# Lock.net
KiCad netlist of a schematic drawn in EAGLE
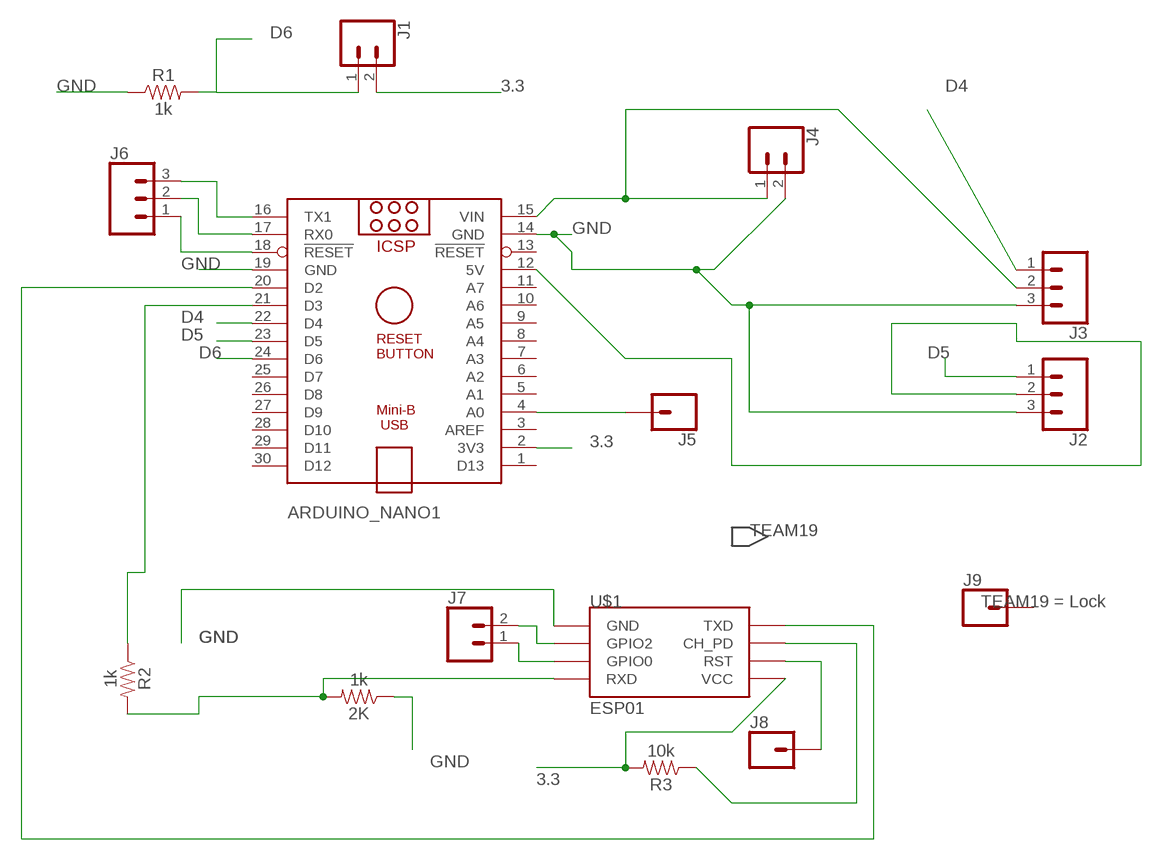
[diagram p0: schematic, sheet 1]

(export (version "E")
  (design (tool "Eeschema 10.0.6"))
  (components
    (comp (ref "2K")
      (value "1k")
      (footprint "eagle-import:AXIAL-0.3")
      (libsource (lib "eagle-import") (part "1KOHM-HORIZ-1/4W-1%"))
    )
    (comp (ref "ARDUINO_NANO1")
      (value "ARDUINO_NANO")
      (footprint "eagle-import:ARDUINO_NANO")
      (libsource (lib "eagle-import") (part "ARDUINO_NANO"))
    )
    (comp (ref "J1")
      (value "CONN_02")
      (footprint "eagle-import:1X02")
      (libsource (lib "eagle-import") (part "CONN_02"))
    )
    (comp (ref "J2")
      (value "CONN_03")
      (footprint "eagle-import:1X03")
      (libsource (lib "eagle-import") (part "CONN_03"))
    )
    (comp (ref "J3")
      (value "CONN_03")
      (footprint "eagle-import:1X03")
      (libsource (lib "eagle-import") (part "CONN_03"))
    )
    (comp (ref "J4")
      (value "CONN_02")
      (footprint "eagle-import:1X02")
      (libsource (lib "eagle-import") (part "CONN_02"))
    )
    (comp (ref "J5")
      (value "CONN_01")
      (footprint "eagle-import:1X01")
      (libsource (lib "eagle-import") (part "CONN_01"))
    )
    (comp (ref "J6")
      (value "CONN_03")
      (footprint "eagle-import:1X03")
      (libsource (lib "eagle-import") (part "CONN_03"))
    )
    (comp (ref "J7")
      (value "CONN_02")
      (footprint "eagle-import:1X02")
      (libsource (lib "eagle-import") (part "CONN_02"))
    )
    (comp (ref "J8")
      (value "CONN_01")
      (footprint "eagle-import:1X01")
      (libsource (lib "eagle-import") (part "CONN_01"))
    )
    (comp (ref "J9")
      (value "CONN_01")
      (footprint "eagle-import:1X01")
      (fields (field (name "TEAM19") "Lock"))
      (libsource (lib "eagle-import") (part "CONN_01"))
    )
    (comp (ref "R1")
      (value "1k")
      (footprint "eagle-import:AXIAL-0.3")
      (libsource (lib "eagle-import") (part "1KOHM-HORIZ-1/4W-1%"))
    )
    (comp (ref "R2")
      (value "1k")
      (footprint "eagle-import:AXIAL-0.3")
      (libsource (lib "eagle-import") (part "1KOHM-HORIZ-1/4W-1%"))
    )
    (comp (ref "R3")
      (value "10k")
      (footprint "eagle-import:AXIAL-0.3")
      (libsource (lib "eagle-import") (part "10KOHM-HORIZ-1/4W-1%"))
    )
    (comp (ref "U$1")
      (value "ESP01")
      (footprint "eagle-import:ESP01")
      (libsource (lib "eagle-import") (part "ESP01"))
    )
  )
  (nets
    (net (code "1") (name "/3.3") (class "Default")
      (node (ref "ARDUINO_NANO1") (pin "2") (pinfunction "3V3_2") (pintype "output"))
      (node (ref "J1") (pin "2") (pinfunction "2_2") (pintype "passive"))
      (node (ref "R3") (pin "P$2") (pinfunction "2_P$2") (pintype "passive"))
      (node (ref "U$1") (pin "VCC") (pinfunction "VCC_VCC") (pintype "bidirectional"))
    )
    (net (code "2") (name "/D4") (class "Default")
      (node (ref "ARDUINO_NANO1") (pin "22") (pinfunction "D4_22") (pintype "bidirectional"))
      (node (ref "J3") (pin "1") (pinfunction "1_1") (pintype "passive"))
    )
    (net (code "3") (name "/D5") (class "Default")
      (node (ref "ARDUINO_NANO1") (pin "23") (pinfunction "D5_23") (pintype "bidirectional"))
      (node (ref "J2") (pin "1") (pinfunction "1_1") (pintype "passive"))
    )
    (net (code "4") (name "/D6") (class "Default")
      (node (ref "ARDUINO_NANO1") (pin "24") (pinfunction "D6_24") (pintype "bidirectional"))
      (node (ref "J1") (pin "1") (pinfunction "1_1") (pintype "passive"))
      (node (ref "R1") (pin "P$2") (pinfunction "2_P$2") (pintype "passive"))
    )
    (net (code "5") (name "/GND") (class "Default")
      (node (ref "2K") (pin "P$1") (pinfunction "1_P$1") (pintype "passive"))
      (node (ref "ARDUINO_NANO1") (pin "14") (pinfunction "GND_14") (pintype "power_in"))
      (node (ref "ARDUINO_NANO1") (pin "19") (pinfunction "GND_19") (pintype "power_in"))
      (node (ref "J2") (pin "3") (pinfunction "3_3") (pintype "passive"))
      (node (ref "J3") (pin "3") (pinfunction "3_3") (pintype "passive"))
      (node (ref "J4") (pin "2") (pinfunction "2_2") (pintype "passive"))
      (node (ref "R1") (pin "P$1") (pinfunction "1_P$1") (pintype "passive"))
      (node (ref "U$1") (pin "GND") (pinfunction "GND_GND") (pintype "bidirectional"))
    )
    (net (code "6") (name "Net-(2K-2)") (class "Default")
      (node (ref "2K") (pin "P$2") (pinfunction "2_P$2") (pintype "passive"))
      (node (ref "R2") (pin "P$2") (pinfunction "2_P$2") (pintype "passive"))
      (node (ref "U$1") (pin "RX") (pinfunction "RXD_RX") (pintype "bidirectional"))
    )
    (net (code "7") (name "Net-(ARDUINO_NANO1-5V)") (class "Default")
      (node (ref "ARDUINO_NANO1") (pin "12") (pinfunction "5V_12") (pintype "power_in"))
      (node (ref "J2") (pin "2") (pinfunction "2_2") (pintype "passive"))
    )
    (net (code "8") (name "Net-(ARDUINO_NANO1-A0)") (class "Default")
      (node (ref "ARDUINO_NANO1") (pin "4") (pinfunction "A0_4") (pintype "bidirectional"))
      (node (ref "J5") (pin "1") (pinfunction "1_1") (pintype "passive"))
    )
    (net (code "9") (name "Net-(ARDUINO_NANO1-D2)") (class "Default")
      (node (ref "ARDUINO_NANO1") (pin "20") (pinfunction "D2_20") (pintype "bidirectional"))
      (node (ref "U$1") (pin "TX") (pinfunction "TXD_TX") (pintype "bidirectional"))
    )
    (net (code "10") (name "Net-(ARDUINO_NANO1-D3)") (class "Default")
      (node (ref "ARDUINO_NANO1") (pin "21") (pinfunction "D3_21") (pintype "bidirectional"))
      (node (ref "R2") (pin "P$1") (pinfunction "1_P$1") (pintype "passive"))
    )
    (net (code "11") (name "Net-(ARDUINO_NANO1-RX0)") (class "Default")
      (node (ref "ARDUINO_NANO1") (pin "17") (pinfunction "RX0_17") (pintype "bidirectional"))
      (node (ref "J6") (pin "2") (pinfunction "2_2") (pintype "passive"))
    )
    (net (code "12") (name "Net-(ARDUINO_NANO1-TX1)") (class "Default")
      (node (ref "ARDUINO_NANO1") (pin "16") (pinfunction "TX1_16") (pintype "bidirectional"))
      (node (ref "J6") (pin "3") (pinfunction "3_3") (pintype "passive"))
    )
    (net (code "13") (name "Net-(ARDUINO_NANO1-VIN)") (class "Default")
      (node (ref "ARDUINO_NANO1") (pin "15") (pinfunction "VIN_15") (pintype "power_in"))
      (node (ref "J3") (pin "2") (pinfunction "2_2") (pintype "passive"))
      (node (ref "J4") (pin "1") (pinfunction "1_1") (pintype "passive"))
    )
    (net (code "14") (name "Net-(ARDUINO_NANO1-~{RESET}-Pad18)") (class "Default")
      (node (ref "ARDUINO_NANO1") (pin "18") (pinfunction "~{RESET}_18") (pintype "input"))
      (node (ref "J6") (pin "1") (pinfunction "1_1") (pintype "passive"))
    )
    (net (code "15") (name "Net-(J7-Pad1)") (class "Default")
      (node (ref "J7") (pin "1") (pinfunction "1_1") (pintype "passive"))
      (node (ref "U$1") (pin "GPIO0") (pinfunction "GPIO0_GPIO0") (pintype "bidirectional"))
    )
    (net (code "16") (name "Net-(J7-Pad2)") (class "Default")
      (node (ref "J7") (pin "2") (pinfunction "2_2") (pintype "passive"))
      (node (ref "U$1") (pin "GPIO2") (pinfunction "GPIO2_GPIO2") (pintype "bidirectional"))
    )
    (net (code "17") (name "Net-(J8-Pad1)") (class "Default")
      (node (ref "J8") (pin "1") (pinfunction "1_1") (pintype "passive"))
      (node (ref "U$1") (pin "RST") (pinfunction "RST_RST") (pintype "bidirectional"))
    )
    (net (code "18") (name "Net-(R3-1)") (class "Default")
      (node (ref "R3") (pin "P$1") (pinfunction "1_P$1") (pintype "passive"))
      (node (ref "U$1") (pin "CH_PD") (pinfunction "CH_PD_CH_PD") (pintype "bidirectional"))
    )
    (net (code "19") (name "unconnected-(ARDUINO_NANO1-A1-Pad5)") (class "Default")
      (node (ref "ARDUINO_NANO1") (pin "5") (pinfunction "A1_5") (pintype "bidirectional"))
    )
    (net (code "20") (name "unconnected-(ARDUINO_NANO1-A2-Pad6)") (class "Default")
      (node (ref "ARDUINO_NANO1") (pin "6") (pinfunction "A2_6") (pintype "bidirectional"))
    )
    (net (code "21") (name "unconnected-(ARDUINO_NANO1-A3-Pad7)") (class "Default")
      (node (ref "ARDUINO_NANO1") (pin "7") (pinfunction "A3_7") (pintype "bidirectional"))
    )
    (net (code "22") (name "unconnected-(ARDUINO_NANO1-A4-Pad8)") (class "Default")
      (node (ref "ARDUINO_NANO1") (pin "8") (pinfunction "A4_8") (pintype "bidirectional"))
    )
    (net (code "23") (name "unconnected-(ARDUINO_NANO1-A5-Pad9)") (class "Default")
      (node (ref "ARDUINO_NANO1") (pin "9") (pinfunction "A5_9") (pintype "bidirectional"))
    )
    (net (code "24") (name "unconnected-(ARDUINO_NANO1-A6-Pad10)") (class "Default")
      (node (ref "ARDUINO_NANO1") (pin "10") (pinfunction "A6_10") (pintype "bidirectional"))
    )
    (net (code "25") (name "unconnected-(ARDUINO_NANO1-A7-Pad11)") (class "Default")
      (node (ref "ARDUINO_NANO1") (pin "11") (pinfunction "A7_11") (pintype "bidirectional"))
    )
    (net (code "26") (name "unconnected-(ARDUINO_NANO1-AREF-Pad3)") (class "Default")
      (node (ref "ARDUINO_NANO1") (pin "3") (pinfunction "AREF_3") (pintype "input"))
    )
    (net (code "27") (name "unconnected-(ARDUINO_NANO1-D7-Pad25)") (class "Default")
      (node (ref "ARDUINO_NANO1") (pin "25") (pinfunction "D7_25") (pintype "bidirectional"))
    )
    (net (code "28") (name "unconnected-(ARDUINO_NANO1-D8-Pad26)") (class "Default")
      (node (ref "ARDUINO_NANO1") (pin "26") (pinfunction "D8_26") (pintype "bidirectional"))
    )
    (net (code "29") (name "unconnected-(ARDUINO_NANO1-D9-Pad27)") (class "Default")
      (node (ref "ARDUINO_NANO1") (pin "27") (pinfunction "D9_27") (pintype "bidirectional"))
    )
    (net (code "30") (name "unconnected-(ARDUINO_NANO1-D10-Pad28)") (class "Default")
      (node (ref "ARDUINO_NANO1") (pin "28") (pinfunction "D10_28") (pintype "bidirectional"))
    )
    (net (code "31") (name "unconnected-(ARDUINO_NANO1-D11-Pad29)") (class "Default")
      (node (ref "ARDUINO_NANO1") (pin "29") (pinfunction "D11_29") (pintype "bidirectional"))
    )
    (net (code "32") (name "unconnected-(ARDUINO_NANO1-D12-Pad30)") (class "Default")
      (node (ref "ARDUINO_NANO1") (pin "30") (pinfunction "D12_30") (pintype "bidirectional"))
    )
    (net (code "33") (name "unconnected-(ARDUINO_NANO1-D13-Pad1)") (class "Default")
      (node (ref "ARDUINO_NANO1") (pin "1") (pinfunction "D13_1") (pintype "bidirectional"))
    )
    (net (code "34") (name "unconnected-(ARDUINO_NANO1-~{RESET}-Pad13)") (class "Default")
      (node (ref "ARDUINO_NANO1") (pin "13") (pinfunction "~{RESET}_13") (pintype "input"))
    )
    (net (code "35") (name "unconnected-(J9-Pad1)") (class "Default")
      (node (ref "J9") (pin "1") (pinfunction "1_1") (pintype "passive"))
    )
  )
)
